# RotaryEncoder.net
KiCad netlist of a schematic drawn in Altium Designer
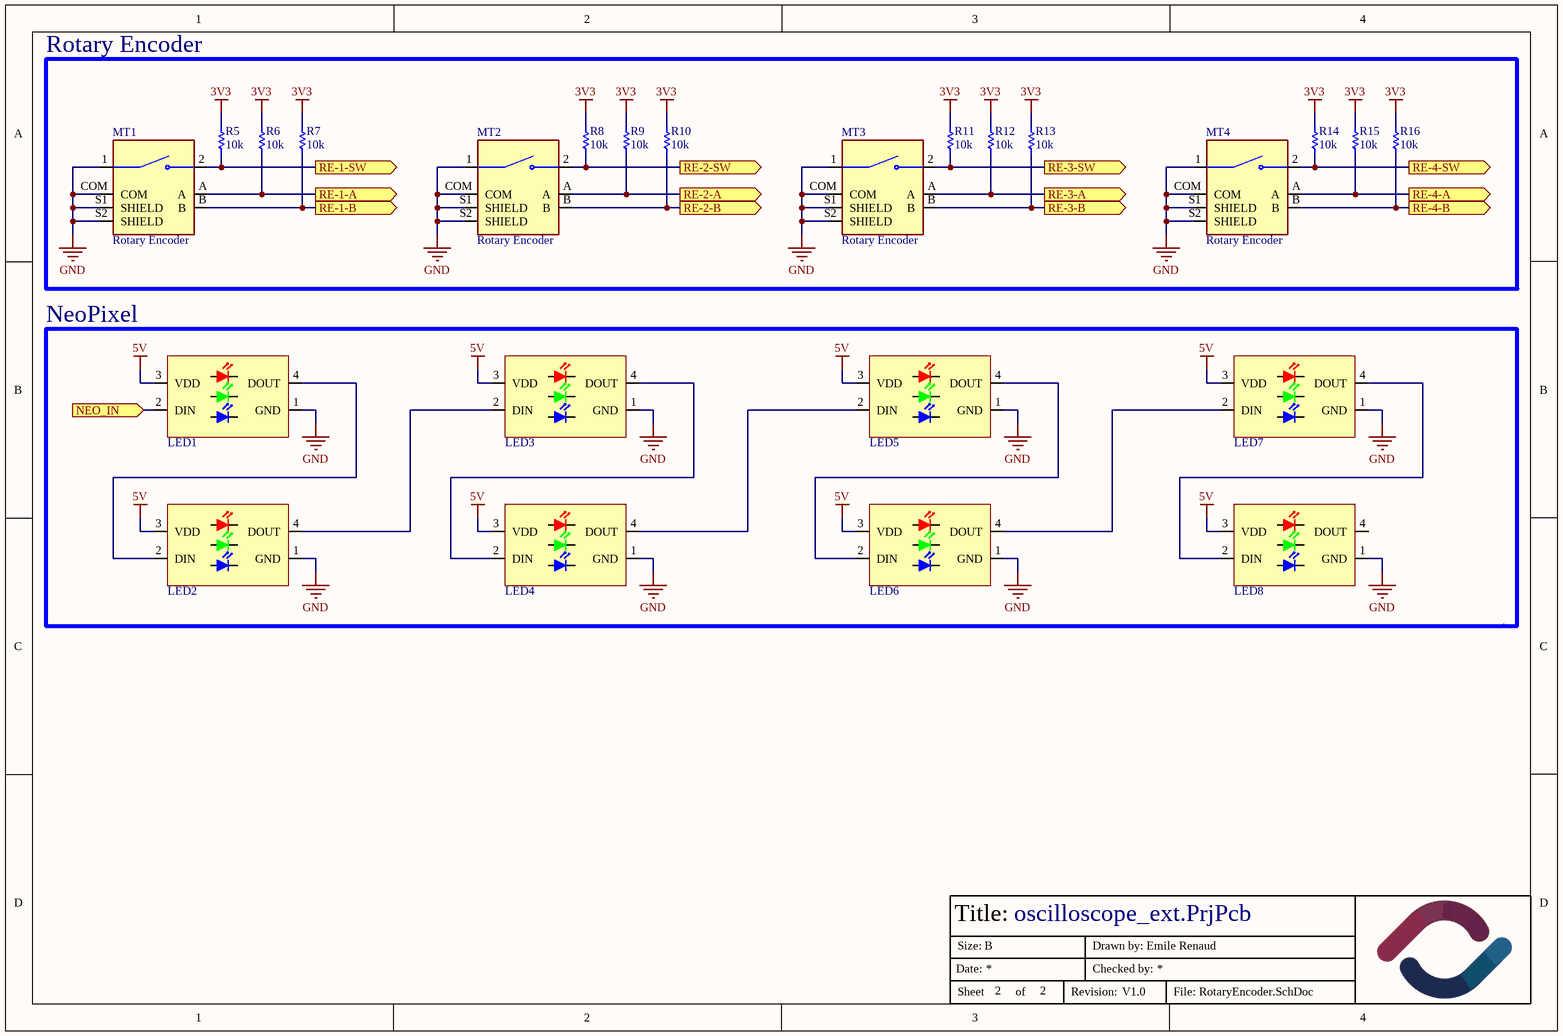
[diagram p0: RotaryEncoder.SchDoc]

(export (version "E")
  (design (tool "Eeschema 10.0.6"))
  (components
    (comp (ref "LED1")
      (value "1528-1104-ND")
      (footprint "LED_NEO")
      (description "LED RGB COMMON CATHODE (0.95(L)X")
      (libsource (lib "LEDs") (part "Led-NeoPixel"))
    )
    (comp (ref "LED2")
      (value "1528-1104-ND")
      (footprint "LED_NEO")
      (description "LED RGB COMMON CATHODE (0.95(L)X")
      (libsource (lib "LEDs") (part "Led-NeoPixel"))
    )
    (comp (ref "LED3")
      (value "1528-1104-ND")
      (footprint "LED_NEO")
      (description "LED RGB COMMON CATHODE (0.95(L)X")
      (libsource (lib "LEDs") (part "Led-NeoPixel"))
    )
    (comp (ref "LED4")
      (value "1528-1104-ND")
      (footprint "LED_NEO")
      (description "LED RGB COMMON CATHODE (0.95(L)X")
      (libsource (lib "LEDs") (part "Led-NeoPixel"))
    )
    (comp (ref "LED5")
      (value "1528-1104-ND")
      (footprint "LED_NEO")
      (description "LED RGB COMMON CATHODE (0.95(L)X")
      (libsource (lib "LEDs") (part "Led-NeoPixel"))
    )
    (comp (ref "LED6")
      (value "1528-1104-ND")
      (footprint "LED_NEO")
      (description "LED RGB COMMON CATHODE (0.95(L)X")
      (libsource (lib "LEDs") (part "Led-NeoPixel"))
    )
    (comp (ref "LED7")
      (value "1528-1104-ND")
      (footprint "LED_NEO")
      (description "LED RGB COMMON CATHODE (0.95(L)X")
      (libsource (lib "LEDs") (part "Led-NeoPixel"))
    )
    (comp (ref "LED8")
      (value "1528-1104-ND")
      (footprint "LED_NEO")
      (description "LED RGB COMMON CATHODE (0.95(L)X")
      (libsource (lib "LEDs") (part "Led-NeoPixel"))
    )
    (comp (ref "MT1")
      (value "Rotary Encoder")
      (footprint "PCB_Footprints:XDCR_PEC11R-4215F-S0024")
      (description "Incremental Encoder, 12 Mm, Contact Rating 10 Ma - 5 Vdc")
      (fields (field (name "MP") "PEC11R-4215F-S0024"))
      (libsource (lib "Encoder") (part "PEC11R-4215F-S0024"))
    )
    (comp (ref "MT2")
      (value "Rotary Encoder")
      (footprint "PCB_Footprints:XDCR_PEC11R-4215F-S0024")
      (description "Incremental Encoder, 12 Mm, Contact Rating 10 Ma - 5 Vdc")
      (fields (field (name "MP") "PEC11R-4215F-S0024"))
      (libsource (lib "Encoder") (part "PEC11R-4215F-S0024"))
    )
    (comp (ref "MT3")
      (value "Rotary Encoder")
      (footprint "PCB_Footprints:XDCR_PEC11R-4215F-S0024")
      (description "Incremental Encoder, 12 Mm, Contact Rating 10 Ma - 5 Vdc")
      (fields (field (name "MP") "PEC11R-4215F-S0024"))
      (libsource (lib "Encoder") (part "PEC11R-4215F-S0024"))
    )
    (comp (ref "MT4")
      (value "Rotary Encoder")
      (footprint "PCB_Footprints:XDCR_PEC11R-4215F-S0024")
      (description "Incremental Encoder, 12 Mm, Contact Rating 10 Ma - 5 Vdc")
      (fields (field (name "MP") "PEC11R-4215F-S0024"))
      (libsource (lib "Encoder") (part "PEC11R-4215F-S0024"))
    )
    (comp (ref "R5")
      (value "10k")
      (footprint "Resistor-0603")
      (description "Resistor0603-10k")
      (fields (field (name "Comment") "SMT resistor"))
      (libsource (lib "Resistors") (part "Resistor0603-10k"))
    )
    (comp (ref "R6")
      (value "10k")
      (footprint "Resistor-0603")
      (description "Resistor0603-10k")
      (fields (field (name "Comment") "SMT resistor"))
      (libsource (lib "Resistors") (part "Resistor0603-10k"))
    )
    (comp (ref "R7")
      (value "10k")
      (footprint "Resistor-0603")
      (description "Resistor0603-10k")
      (fields (field (name "Comment") "SMT resistor"))
      (libsource (lib "Resistors") (part "Resistor0603-10k"))
    )
    (comp (ref "R8")
      (value "10k")
      (footprint "Resistor-0603")
      (description "Resistor0603-10k")
      (fields (field (name "Comment") "SMT resistor"))
      (libsource (lib "Resistors") (part "Resistor0603-10k"))
    )
    (comp (ref "R9")
      (value "10k")
      (footprint "Resistor-0603")
      (description "Resistor0603-10k")
      (fields (field (name "Comment") "SMT resistor"))
      (libsource (lib "Resistors") (part "Resistor0603-10k"))
    )
    (comp (ref "R10")
      (value "10k")
      (footprint "Resistor-0603")
      (description "Resistor0603-10k")
      (fields (field (name "Comment") "SMT resistor"))
      (libsource (lib "Resistors") (part "Resistor0603-10k"))
    )
    (comp (ref "R11")
      (value "10k")
      (footprint "Resistor-0603")
      (description "Resistor0603-10k")
      (fields (field (name "Comment") "SMT resistor"))
      (libsource (lib "Resistors") (part "Resistor0603-10k"))
    )
    (comp (ref "R12")
      (value "10k")
      (footprint "Resistor-0603")
      (description "Resistor0603-10k")
      (fields (field (name "Comment") "SMT resistor"))
      (libsource (lib "Resistors") (part "Resistor0603-10k"))
    )
    (comp (ref "R13")
      (value "10k")
      (footprint "Resistor-0603")
      (description "Resistor0603-10k")
      (fields (field (name "Comment") "SMT resistor"))
      (libsource (lib "Resistors") (part "Resistor0603-10k"))
    )
    (comp (ref "R14")
      (value "10k")
      (footprint "Resistor-0603")
      (description "Resistor0603-10k")
      (fields (field (name "Comment") "SMT resistor"))
      (libsource (lib "Resistors") (part "Resistor0603-10k"))
    )
    (comp (ref "R15")
      (value "10k")
      (footprint "Resistor-0603")
      (description "Resistor0603-10k")
      (fields (field (name "Comment") "SMT resistor"))
      (libsource (lib "Resistors") (part "Resistor0603-10k"))
    )
    (comp (ref "R16")
      (value "10k")
      (footprint "Resistor-0603")
      (description "Resistor0603-10k")
      (fields (field (name "Comment") "SMT resistor"))
      (libsource (lib "Resistors") (part "Resistor0603-10k"))
    )
  )
  (nets
    (net (code "1") (name "/NEO_IN") (class "Default")
      (node (ref "LED1") (pin "2") (pinfunction "DIN_2") (pintype "passive"))
    )
    (net (code "2") (name "/RE-1-A") (class "Default")
      (node (ref "MT1") (pin "A") (pinfunction "A_A") (pintype "passive"))
      (node (ref "R6") (pin "1") (pinfunction "1_1") (pintype "passive"))
    )
    (net (code "3") (name "/RE-1-B") (class "Default")
      (node (ref "MT1") (pin "B") (pinfunction "B_B") (pintype "passive"))
      (node (ref "R7") (pin "1") (pinfunction "1_1") (pintype "passive"))
    )
    (net (code "4") (name "/RE-1-SW") (class "Default")
      (node (ref "MT1") (pin "2") (pinfunction "2_2") (pintype "passive"))
      (node (ref "R5") (pin "1") (pinfunction "1_1") (pintype "passive"))
    )
    (net (code "5") (name "/RE-2-A") (class "Default")
      (node (ref "MT2") (pin "A") (pinfunction "A_A") (pintype "passive"))
      (node (ref "R9") (pin "1") (pinfunction "1_1") (pintype "passive"))
    )
    (net (code "6") (name "/RE-2-B") (class "Default")
      (node (ref "MT2") (pin "B") (pinfunction "B_B") (pintype "passive"))
      (node (ref "R10") (pin "1") (pinfunction "1_1") (pintype "passive"))
    )
    (net (code "7") (name "/RE-2-SW") (class "Default")
      (node (ref "MT2") (pin "2") (pinfunction "2_2") (pintype "passive"))
      (node (ref "R8") (pin "1") (pinfunction "1_1") (pintype "passive"))
    )
    (net (code "8") (name "/RE-3-A") (class "Default")
      (node (ref "MT3") (pin "A") (pinfunction "A_A") (pintype "passive"))
      (node (ref "R12") (pin "1") (pinfunction "1_1") (pintype "passive"))
    )
    (net (code "9") (name "/RE-3-B") (class "Default")
      (node (ref "MT3") (pin "B") (pinfunction "B_B") (pintype "passive"))
      (node (ref "R13") (pin "1") (pinfunction "1_1") (pintype "passive"))
    )
    (net (code "10") (name "/RE-3-SW") (class "Default")
      (node (ref "MT3") (pin "2") (pinfunction "2_2") (pintype "passive"))
      (node (ref "R11") (pin "1") (pinfunction "1_1") (pintype "passive"))
    )
    (net (code "11") (name "/RE-4-A") (class "Default")
      (node (ref "MT4") (pin "A") (pinfunction "A_A") (pintype "passive"))
      (node (ref "R15") (pin "1") (pinfunction "1_1") (pintype "passive"))
    )
    (net (code "12") (name "/RE-4-B") (class "Default")
      (node (ref "MT4") (pin "B") (pinfunction "B_B") (pintype "passive"))
      (node (ref "R16") (pin "1") (pinfunction "1_1") (pintype "passive"))
    )
    (net (code "13") (name "/RE-4-SW") (class "Default")
      (node (ref "MT4") (pin "2") (pinfunction "2_2") (pintype "passive"))
      (node (ref "R14") (pin "1") (pinfunction "1_1") (pintype "passive"))
    )
    (net (code "14") (name "3V3") (class "Default")
      (node (ref "R10") (pin "2") (pinfunction "2_2") (pintype "passive"))
      (node (ref "R11") (pin "2") (pinfunction "2_2") (pintype "passive"))
      (node (ref "R12") (pin "2") (pinfunction "2_2") (pintype "passive"))
      (node (ref "R13") (pin "2") (pinfunction "2_2") (pintype "passive"))
      (node (ref "R14") (pin "2") (pinfunction "2_2") (pintype "passive"))
      (node (ref "R15") (pin "2") (pinfunction "2_2") (pintype "passive"))
      (node (ref "R16") (pin "2") (pinfunction "2_2") (pintype "passive"))
      (node (ref "R5") (pin "2") (pinfunction "2_2") (pintype "passive"))
      (node (ref "R6") (pin "2") (pinfunction "2_2") (pintype "passive"))
      (node (ref "R7") (pin "2") (pinfunction "2_2") (pintype "passive"))
      (node (ref "R8") (pin "2") (pinfunction "2_2") (pintype "passive"))
      (node (ref "R9") (pin "2") (pinfunction "2_2") (pintype "passive"))
    )
    (net (code "15") (name "5V") (class "Default")
      (node (ref "LED1") (pin "3") (pinfunction "VDD_3") (pintype "passive"))
      (node (ref "LED2") (pin "3") (pinfunction "VDD_3") (pintype "passive"))
      (node (ref "LED3") (pin "3") (pinfunction "VDD_3") (pintype "passive"))
      (node (ref "LED4") (pin "3") (pinfunction "VDD_3") (pintype "passive"))
      (node (ref "LED5") (pin "3") (pinfunction "VDD_3") (pintype "passive"))
      (node (ref "LED6") (pin "3") (pinfunction "VDD_3") (pintype "passive"))
      (node (ref "LED7") (pin "3") (pinfunction "VDD_3") (pintype "passive"))
      (node (ref "LED8") (pin "3") (pinfunction "VDD_3") (pintype "passive"))
    )
    (net (code "16") (name "GND") (class "Default")
      (node (ref "LED1") (pin "1") (pinfunction "GND_1") (pintype "passive"))
      (node (ref "LED2") (pin "1") (pinfunction "GND_1") (pintype "passive"))
      (node (ref "LED3") (pin "1") (pinfunction "GND_1") (pintype "passive"))
      (node (ref "LED4") (pin "1") (pinfunction "GND_1") (pintype "passive"))
      (node (ref "LED5") (pin "1") (pinfunction "GND_1") (pintype "passive"))
      (node (ref "LED6") (pin "1") (pinfunction "GND_1") (pintype "passive"))
      (node (ref "LED7") (pin "1") (pinfunction "GND_1") (pintype "passive"))
      (node (ref "LED8") (pin "1") (pinfunction "GND_1") (pintype "passive"))
      (node (ref "MT1") (pin "1") (pinfunction "1_1") (pintype "passive"))
      (node (ref "MT1") (pin "COM") (pinfunction "COM_COM") (pintype "passive"))
      (node (ref "MT1") (pin "S1") (pinfunction "SHIELD_S1") (pintype "passive"))
      (node (ref "MT1") (pin "S2") (pinfunction "SHIELD_S2") (pintype "passive"))
      (node (ref "MT2") (pin "1") (pinfunction "1_1") (pintype "passive"))
      (node (ref "MT2") (pin "COM") (pinfunction "COM_COM") (pintype "passive"))
      (node (ref "MT2") (pin "S1") (pinfunction "SHIELD_S1") (pintype "passive"))
      (node (ref "MT2") (pin "S2") (pinfunction "SHIELD_S2") (pintype "passive"))
      (node (ref "MT3") (pin "1") (pinfunction "1_1") (pintype "passive"))
      (node (ref "MT3") (pin "COM") (pinfunction "COM_COM") (pintype "passive"))
      (node (ref "MT3") (pin "S1") (pinfunction "SHIELD_S1") (pintype "passive"))
      (node (ref "MT3") (pin "S2") (pinfunction "SHIELD_S2") (pintype "passive"))
      (node (ref "MT4") (pin "1") (pinfunction "1_1") (pintype "passive"))
      (node (ref "MT4") (pin "COM") (pinfunction "COM_COM") (pintype "passive"))
      (node (ref "MT4") (pin "S1") (pinfunction "SHIELD_S1") (pintype "passive"))
      (node (ref "MT4") (pin "S2") (pinfunction "SHIELD_S2") (pintype "passive"))
    )
    (net (code "17") (name "Net-(LED1-DOUT)") (class "Default")
      (node (ref "LED1") (pin "4") (pinfunction "DOUT_4") (pintype "passive"))
      (node (ref "LED2") (pin "2") (pinfunction "DIN_2") (pintype "passive"))
    )
    (net (code "18") (name "Net-(LED2-DOUT)") (class "Default")
      (node (ref "LED2") (pin "4") (pinfunction "DOUT_4") (pintype "passive"))
      (node (ref "LED3") (pin "2") (pinfunction "DIN_2") (pintype "passive"))
    )
    (net (code "19") (name "Net-(LED3-DOUT)") (class "Default")
      (node (ref "LED3") (pin "4") (pinfunction "DOUT_4") (pintype "passive"))
      (node (ref "LED4") (pin "2") (pinfunction "DIN_2") (pintype "passive"))
    )
    (net (code "20") (name "Net-(LED4-DOUT)") (class "Default")
      (node (ref "LED4") (pin "4") (pinfunction "DOUT_4") (pintype "passive"))
      (node (ref "LED5") (pin "2") (pinfunction "DIN_2") (pintype "passive"))
    )
    (net (code "21") (name "Net-(LED5-DOUT)") (class "Default")
      (node (ref "LED5") (pin "4") (pinfunction "DOUT_4") (pintype "passive"))
      (node (ref "LED6") (pin "2") (pinfunction "DIN_2") (pintype "passive"))
    )
    (net (code "22") (name "Net-(LED6-DOUT)") (class "Default")
      (node (ref "LED6") (pin "4") (pinfunction "DOUT_4") (pintype "passive"))
      (node (ref "LED7") (pin "2") (pinfunction "DIN_2") (pintype "passive"))
    )
    (net (code "23") (name "Net-(LED7-DOUT)") (class "Default")
      (node (ref "LED7") (pin "4") (pinfunction "DOUT_4") (pintype "passive"))
      (node (ref "LED8") (pin "2") (pinfunction "DIN_2") (pintype "passive"))
    )
    (net (code "24") (name "unconnected-(LED8-DOUT-Pad4)") (class "Default")
      (node (ref "LED8") (pin "4") (pinfunction "DOUT_4") (pintype "passive"))
    )
  )
)
